# greenhouse_huzah_feather.net
KiCad netlist of a schematic drawn in EAGLE
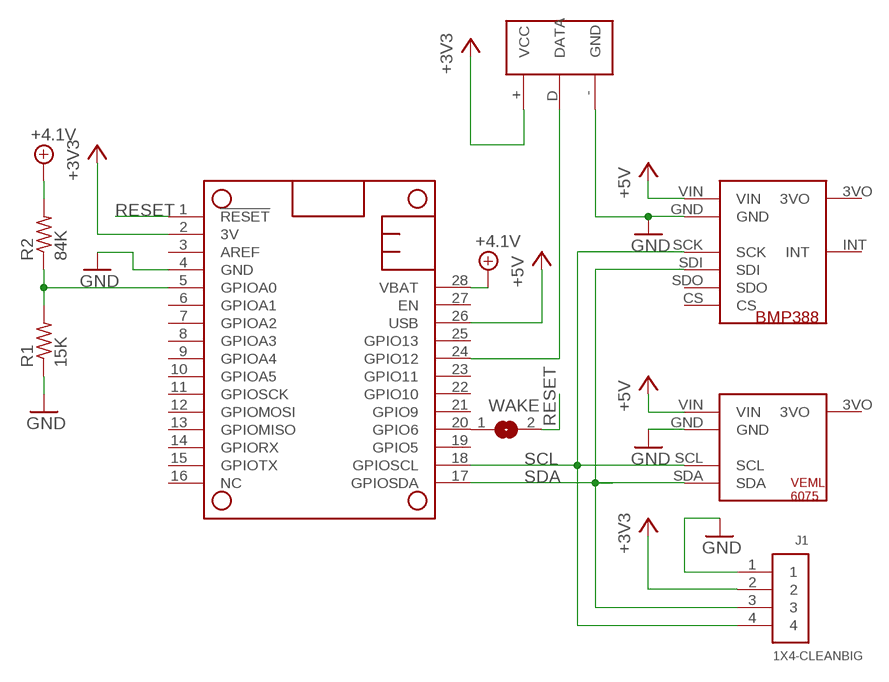
[diagram p0: schematic, sheet 1]

(export (version "E")
  (design (tool "Eeschema 10.0.6"))
  (components
    (comp (ref "J1")
      (value "1X4-CLEANBIG")
      (footprint "eagle-import:1X04-CLEANBIG")
      (libsource (lib "eagle-import") (part "1X4-CLEANBIG"))
    )
    (comp (ref "MS1")
      (value "FEATHERWING")
      (footprint "eagle-import:FEATHERWING")
      (libsource (lib "eagle-import") (part "FEATHERWING"))
    )
    (comp (ref "R1")
      (value "15K")
      (footprint "eagle-import:R0805")
      (libsource (lib "eagle-import") (part "R-US_R0805"))
    )
    (comp (ref "R2")
      (value "84K")
      (footprint "eagle-import:R0805")
      (libsource (lib "eagle-import") (part "R-US_R0805"))
    )
    (comp (ref "U$1")
      (value "ADA_BMP388")
      (footprint "eagle-import:ADA_BMP388")
      (libsource (lib "eagle-import") (part "ADA_BMP388"))
    )
    (comp (ref "U$2")
      (value "ADA_VEML6075")
      (footprint "eagle-import:ADA_VEML6075")
      (libsource (lib "eagle-import") (part "ADA_VEML6075"))
    )
    (comp (ref "U$4")
      (value "DHT11")
      (footprint "eagle-import:DHT22_DAUGHTER")
      (libsource (lib "eagle-import") (part "DHT11"))
    )
    (comp (ref "WAKE")
      (value "SJ")
      (footprint "eagle-import:SJ")
      (libsource (lib "eagle-import") (part "SJ"))
    )
  )
  (nets
    (net (code "1") (name "+3V3") (class "Default")
      (node (ref "J1") (pin "2") (pinfunction "2_2") (pintype "bidirectional"))
      (node (ref "MS1") (pin "2") (pinfunction "3V_2") (pintype "power_in"))
      (node (ref "U$4") (pin "+") (pinfunction "VCC_+") (pintype "bidirectional"))
    )
    (net (code "2") (name "+4.1V") (class "Default")
      (node (ref "MS1") (pin "28") (pinfunction "VBAT_28") (pintype "power_in"))
      (node (ref "R2") (pin "2") (pinfunction "2_2") (pintype "passive"))
    )
    (net (code "3") (name "+5V") (class "Default")
      (node (ref "MS1") (pin "26") (pinfunction "USB_26") (pintype "power_in"))
      (node (ref "U$1") (pin "VIN") (pinfunction "VIN_VIN") (pintype "bidirectional"))
      (node (ref "U$2") (pin "VIN") (pinfunction "VIN_VIN") (pintype "bidirectional"))
    )
    (net (code "4") (name "/RESET") (class "Default")
      (node (ref "MS1") (pin "1") (pinfunction "~{RESET}_1") (pintype "input"))
      (node (ref "WAKE") (pin "2") (pinfunction "2_2") (pintype "passive"))
    )
    (net (code "5") (name "/SCL") (class "Default")
      (node (ref "J1") (pin "4") (pinfunction "4_4") (pintype "bidirectional"))
      (node (ref "MS1") (pin "18") (pinfunction "GPIOSCL_18") (pintype "bidirectional"))
      (node (ref "U$1") (pin "SCK") (pinfunction "SCK_SCK") (pintype "bidirectional"))
      (node (ref "U$2") (pin "SCL") (pinfunction "SCL_SCL") (pintype "bidirectional"))
    )
    (net (code "6") (name "/SDA") (class "Default")
      (node (ref "J1") (pin "3") (pinfunction "3_3") (pintype "bidirectional"))
      (node (ref "MS1") (pin "17") (pinfunction "GPIOSDA_17") (pintype "bidirectional"))
      (node (ref "U$1") (pin "SDI") (pinfunction "SDI_SDI") (pintype "bidirectional"))
      (node (ref "U$2") (pin "SDA") (pinfunction "SDA_SDA") (pintype "bidirectional"))
    )
    (net (code "7") (name "GND") (class "Default")
      (node (ref "J1") (pin "1") (pinfunction "1_1") (pintype "bidirectional"))
      (node (ref "MS1") (pin "4") (pinfunction "GND_4") (pintype "power_in"))
      (node (ref "R1") (pin "1") (pinfunction "1_1") (pintype "passive"))
      (node (ref "U$1") (pin "GND") (pinfunction "GND_GND") (pintype "bidirectional"))
      (node (ref "U$2") (pin "GND") (pinfunction "GND_GND") (pintype "bidirectional"))
      (node (ref "U$4") (pin "-") (pinfunction "GND_-") (pintype "bidirectional"))
    )
    (net (code "8") (name "Net-(MS1-GPIO6)") (class "Default")
      (node (ref "MS1") (pin "20") (pinfunction "GPIO6_20") (pintype "bidirectional"))
      (node (ref "WAKE") (pin "1") (pinfunction "1_1") (pintype "passive"))
    )
    (net (code "9") (name "Net-(MS1-GPIO12)") (class "Default")
      (node (ref "MS1") (pin "24") (pinfunction "GPIO12_24") (pintype "bidirectional"))
      (node (ref "U$4") (pin "D") (pinfunction "DATA_D") (pintype "bidirectional"))
    )
    (net (code "10") (name "Net-(MS1-GPIOA0)") (class "Default")
      (node (ref "MS1") (pin "5") (pinfunction "GPIOA0_5") (pintype "bidirectional"))
      (node (ref "R1") (pin "2") (pinfunction "2_2") (pintype "passive"))
      (node (ref "R2") (pin "1") (pinfunction "1_1") (pintype "passive"))
    )
    (net (code "11") (name "unconnected-(MS1-AREF-Pad3)") (class "Default")
      (node (ref "MS1") (pin "3") (pinfunction "AREF_3") (pintype "passive"))
    )
    (net (code "12") (name "unconnected-(MS1-EN-Pad27)") (class "Default")
      (node (ref "MS1") (pin "27") (pinfunction "EN_27") (pintype "passive"))
    )
    (net (code "13") (name "unconnected-(MS1-GPIO5-Pad19)") (class "Default")
      (node (ref "MS1") (pin "19") (pinfunction "GPIO5_19") (pintype "bidirectional"))
    )
    (net (code "14") (name "unconnected-(MS1-GPIO9-Pad21)") (class "Default")
      (node (ref "MS1") (pin "21") (pinfunction "GPIO9_21") (pintype "bidirectional"))
    )
    (net (code "15") (name "unconnected-(MS1-GPIO10-Pad22)") (class "Default")
      (node (ref "MS1") (pin "22") (pinfunction "GPIO10_22") (pintype "bidirectional"))
    )
    (net (code "16") (name "unconnected-(MS1-GPIO11-Pad23)") (class "Default")
      (node (ref "MS1") (pin "23") (pinfunction "GPIO11_23") (pintype "bidirectional"))
    )
    (net (code "17") (name "unconnected-(MS1-GPIO13-Pad25)") (class "Default")
      (node (ref "MS1") (pin "25") (pinfunction "GPIO13_25") (pintype "bidirectional"))
    )
    (net (code "18") (name "unconnected-(MS1-GPIOA1-Pad6)") (class "Default")
      (node (ref "MS1") (pin "6") (pinfunction "GPIOA1_6") (pintype "bidirectional"))
    )
    (net (code "19") (name "unconnected-(MS1-GPIOA2-Pad7)") (class "Default")
      (node (ref "MS1") (pin "7") (pinfunction "GPIOA2_7") (pintype "bidirectional"))
    )
    (net (code "20") (name "unconnected-(MS1-GPIOA3-Pad8)") (class "Default")
      (node (ref "MS1") (pin "8") (pinfunction "GPIOA3_8") (pintype "bidirectional"))
    )
    (net (code "21") (name "unconnected-(MS1-GPIOA4-Pad9)") (class "Default")
      (node (ref "MS1") (pin "9") (pinfunction "GPIOA4_9") (pintype "bidirectional"))
    )
    (net (code "22") (name "unconnected-(MS1-GPIOA5-Pad10)") (class "Default")
      (node (ref "MS1") (pin "10") (pinfunction "GPIOA5_10") (pintype "bidirectional"))
    )
    (net (code "23") (name "unconnected-(MS1-GPIOMISO-Pad13)") (class "Default")
      (node (ref "MS1") (pin "13") (pinfunction "GPIOMISO_13") (pintype "bidirectional"))
    )
    (net (code "24") (name "unconnected-(MS1-GPIOMOSI-Pad12)") (class "Default")
      (node (ref "MS1") (pin "12") (pinfunction "GPIOMOSI_12") (pintype "bidirectional"))
    )
    (net (code "25") (name "unconnected-(MS1-GPIORX-Pad14)") (class "Default")
      (node (ref "MS1") (pin "14") (pinfunction "GPIORX_14") (pintype "bidirectional"))
    )
    (net (code "26") (name "unconnected-(MS1-GPIOSCK-Pad11)") (class "Default")
      (node (ref "MS1") (pin "11") (pinfunction "GPIOSCK_11") (pintype "bidirectional"))
    )
    (net (code "27") (name "unconnected-(MS1-GPIOTX-Pad15)") (class "Default")
      (node (ref "MS1") (pin "15") (pinfunction "GPIOTX_15") (pintype "bidirectional"))
    )
    (net (code "28") (name "unconnected-(MS1-NC-Pad16)") (class "Default")
      (node (ref "MS1") (pin "16") (pinfunction "NC_16") (pintype "passive"))
    )
    (net (code "29") (name "unconnected-(U$1-Pad3VO)") (class "Default")
      (node (ref "U$1") (pin "3VO") (pinfunction "3VO_3VO") (pintype "bidirectional"))
    )
    (net (code "30") (name "unconnected-(U$1-PadCS)") (class "Default")
      (node (ref "U$1") (pin "CS") (pinfunction "CS_CS") (pintype "bidirectional"))
    )
    (net (code "31") (name "unconnected-(U$1-PadINT)") (class "Default")
      (node (ref "U$1") (pin "INT") (pinfunction "INT_INT") (pintype "bidirectional"))
    )
    (net (code "32") (name "unconnected-(U$1-PadSDO)") (class "Default")
      (node (ref "U$1") (pin "SDO") (pinfunction "SDO_SDO") (pintype "bidirectional"))
    )
    (net (code "33") (name "unconnected-(U$2-Pad3VO)") (class "Default")
      (node (ref "U$2") (pin "3VO") (pinfunction "3VO_3VO") (pintype "bidirectional"))
    )
  )
)
